# KeyInput_IJMEF.net
KiCad netlist of a schematic drawn in Altium Designer
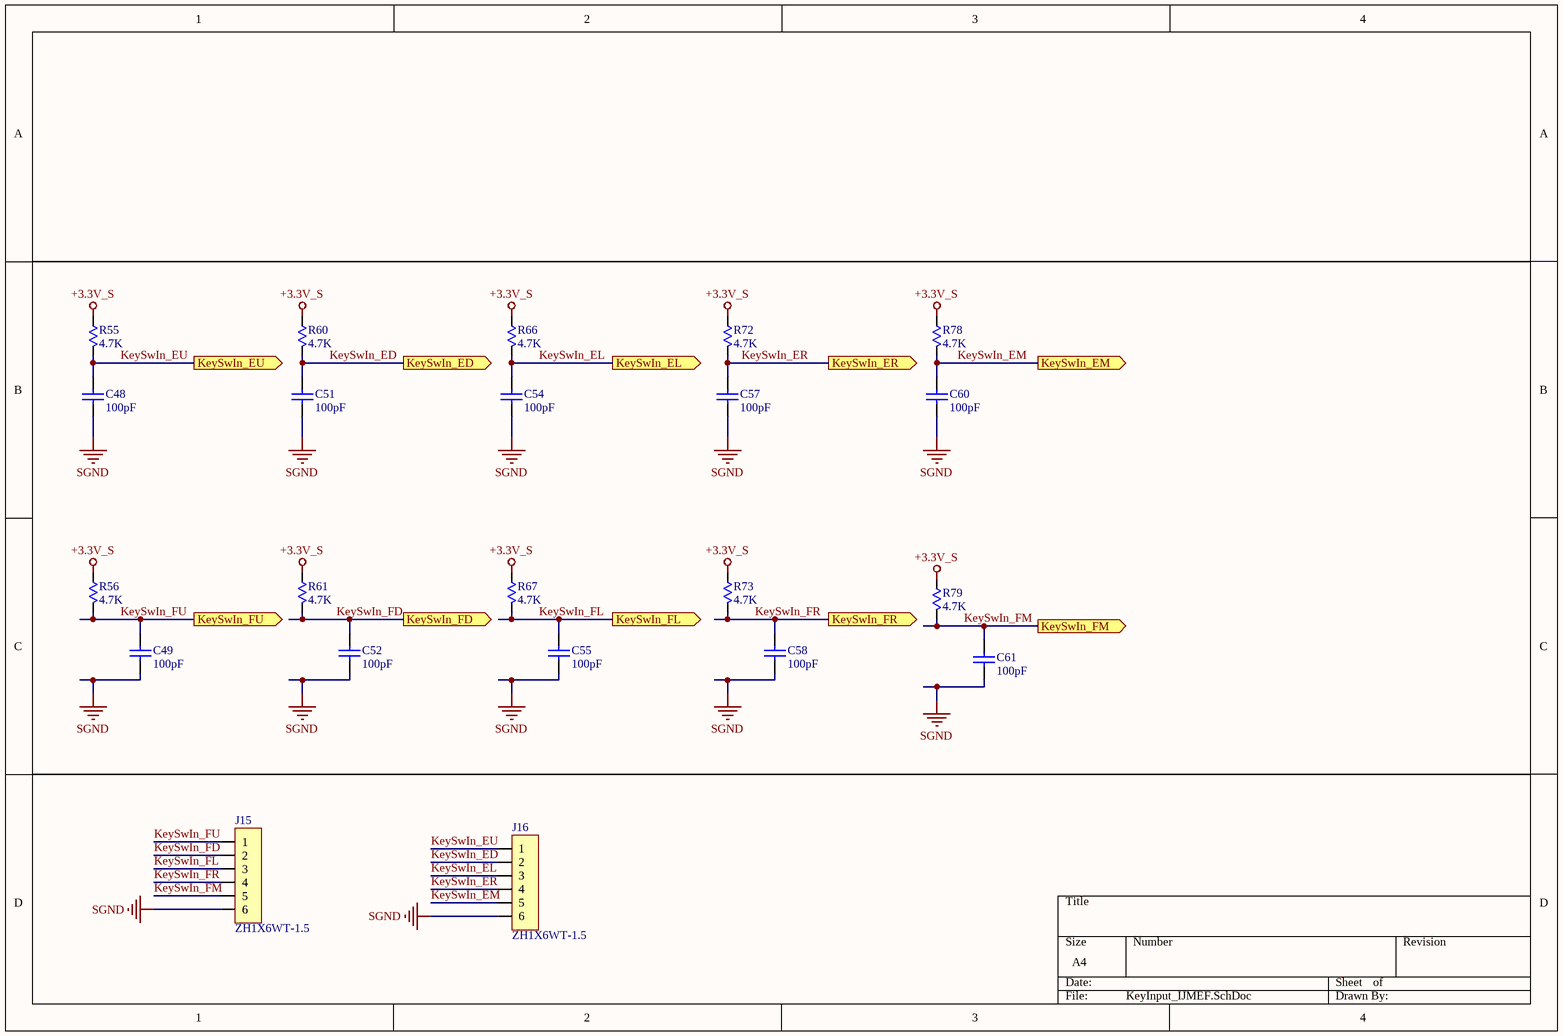
[diagram p0: KeyInput_IJMEF.SchDoc]

(export (version "E")
  (design (tool "Eeschema 10.0.6"))
  (components
    (comp (ref "C48")
      (value "100pF")
      (footprint "C0805")
      (description "Capacitor")
      (fields (field (name "PUBLISHER") "Altium Limited"))
      (libsource (lib "Miscellaneous Devices") (part "Cap"))
    )
    (comp (ref "C49")
      (value "100pF")
      (footprint "C0805")
      (description "Capacitor")
      (fields (field (name "PUBLISHER") "Altium Limited"))
      (libsource (lib "Miscellaneous Devices") (part "Cap"))
    )
    (comp (ref "C51")
      (value "100pF")
      (footprint "C0805")
      (description "Capacitor")
      (fields (field (name "PUBLISHER") "Altium Limited"))
      (libsource (lib "Miscellaneous Devices") (part "Cap"))
    )
    (comp (ref "C52")
      (value "100pF")
      (footprint "C0805")
      (description "Capacitor")
      (fields (field (name "PUBLISHER") "Altium Limited"))
      (libsource (lib "Miscellaneous Devices") (part "Cap"))
    )
    (comp (ref "C54")
      (value "100pF")
      (footprint "C0805")
      (description "Capacitor")
      (fields (field (name "PUBLISHER") "Altium Limited"))
      (libsource (lib "Miscellaneous Devices") (part "Cap"))
    )
    (comp (ref "C55")
      (value "100pF")
      (footprint "C0805")
      (description "Capacitor")
      (fields (field (name "PUBLISHER") "Altium Limited"))
      (libsource (lib "Miscellaneous Devices") (part "Cap"))
    )
    (comp (ref "C57")
      (value "100pF")
      (footprint "C0805")
      (description "Capacitor")
      (fields (field (name "PUBLISHER") "Altium Limited"))
      (libsource (lib "Miscellaneous Devices") (part "Cap"))
    )
    (comp (ref "C58")
      (value "100pF")
      (footprint "C0805")
      (description "Capacitor")
      (fields (field (name "PUBLISHER") "Altium Limited"))
      (libsource (lib "Miscellaneous Devices") (part "Cap"))
    )
    (comp (ref "C60")
      (value "100pF")
      (footprint "C0805")
      (description "Capacitor")
      (fields (field (name "PUBLISHER") "Altium Limited"))
      (libsource (lib "Miscellaneous Devices") (part "Cap"))
    )
    (comp (ref "C61")
      (value "100pF")
      (footprint "C0805")
      (description "Capacitor")
      (fields (field (name "PUBLISHER") "Altium Limited"))
      (libsource (lib "Miscellaneous Devices") (part "Cap"))
    )
    (comp (ref "J15")
      (value "ZH1X6WT-1.5")
      (footprint "ZH1X6WT-1.5")
      (libsource (lib "Connector Class") (part "HEADER1X6"))
    )
    (comp (ref "J16")
      (value "ZH1X6WT-1.5")
      (footprint "ZH1X6WT-1.5")
      (libsource (lib "Connector Class") (part "HEADER1X6"))
    )
    (comp (ref "R55")
      (value "4.7K")
      (footprint "R0805")
      (description "Resistor")
      (fields (field (name "PUBLISHER") "Altium Limited"))
      (libsource (lib "Passive Components Class") (part "RES"))
    )
    (comp (ref "R56")
      (value "4.7K")
      (footprint "R0805")
      (description "Resistor")
      (fields (field (name "PUBLISHER") "Altium Limited"))
      (libsource (lib "Passive Components Class") (part "RES"))
    )
    (comp (ref "R60")
      (value "4.7K")
      (footprint "R0805")
      (description "Resistor")
      (fields (field (name "PUBLISHER") "Altium Limited"))
      (libsource (lib "Passive Components Class") (part "RES"))
    )
    (comp (ref "R61")
      (value "4.7K")
      (footprint "R0805")
      (description "Resistor")
      (fields (field (name "PUBLISHER") "Altium Limited"))
      (libsource (lib "Passive Components Class") (part "RES"))
    )
    (comp (ref "R66")
      (value "4.7K")
      (footprint "R0805")
      (description "Resistor")
      (fields (field (name "PUBLISHER") "Altium Limited"))
      (libsource (lib "Passive Components Class") (part "RES"))
    )
    (comp (ref "R67")
      (value "4.7K")
      (footprint "R0805")
      (description "Resistor")
      (fields (field (name "PUBLISHER") "Altium Limited"))
      (libsource (lib "Passive Components Class") (part "RES"))
    )
    (comp (ref "R72")
      (value "4.7K")
      (footprint "R0805")
      (description "Resistor")
      (fields (field (name "PUBLISHER") "Altium Limited"))
      (libsource (lib "Passive Components Class") (part "RES"))
    )
    (comp (ref "R73")
      (value "4.7K")
      (footprint "R0805")
      (description "Resistor")
      (fields (field (name "PUBLISHER") "Altium Limited"))
      (libsource (lib "Passive Components Class") (part "RES"))
    )
    (comp (ref "R78")
      (value "4.7K")
      (footprint "R0805")
      (description "Resistor")
      (fields (field (name "PUBLISHER") "Altium Limited"))
      (libsource (lib "Passive Components Class") (part "RES"))
    )
    (comp (ref "R79")
      (value "4.7K")
      (footprint "R0805")
      (description "Resistor")
      (fields (field (name "PUBLISHER") "Altium Limited"))
      (libsource (lib "Passive Components Class") (part "RES"))
    )
  )
  (nets
    (net (code "1") (name "+3.3V_S") (class "Default")
      (node (ref "R55") (pin "2") (pinfunction "2_2") (pintype "passive"))
      (node (ref "R56") (pin "2") (pinfunction "2_2") (pintype "passive"))
      (node (ref "R60") (pin "2") (pinfunction "2_2") (pintype "passive"))
      (node (ref "R61") (pin "2") (pinfunction "2_2") (pintype "passive"))
      (node (ref "R66") (pin "2") (pinfunction "2_2") (pintype "passive"))
      (node (ref "R67") (pin "2") (pinfunction "2_2") (pintype "passive"))
      (node (ref "R72") (pin "2") (pinfunction "2_2") (pintype "passive"))
      (node (ref "R73") (pin "2") (pinfunction "2_2") (pintype "passive"))
      (node (ref "R78") (pin "2") (pinfunction "2_2") (pintype "passive"))
      (node (ref "R79") (pin "2") (pinfunction "2_2") (pintype "passive"))
    )
    (net (code "2") (name "/KeySwIn_ED") (class "Default")
      (node (ref "C51") (pin "1") (pinfunction "1_1") (pintype "passive"))
      (node (ref "J16") (pin "2") (pinfunction "2_2") (pintype "passive"))
      (node (ref "R60") (pin "1") (pinfunction "1_1") (pintype "passive"))
    )
    (net (code "3") (name "/KeySwIn_EL") (class "Default")
      (node (ref "C54") (pin "1") (pinfunction "1_1") (pintype "passive"))
      (node (ref "J16") (pin "3") (pinfunction "3_3") (pintype "passive"))
      (node (ref "R66") (pin "1") (pinfunction "1_1") (pintype "passive"))
    )
    (net (code "4") (name "/KeySwIn_EM") (class "Default")
      (node (ref "C60") (pin "1") (pinfunction "1_1") (pintype "passive"))
      (node (ref "J16") (pin "5") (pinfunction "5_5") (pintype "passive"))
      (node (ref "R78") (pin "1") (pinfunction "1_1") (pintype "passive"))
    )
    (net (code "5") (name "/KeySwIn_ER") (class "Default")
      (node (ref "C57") (pin "1") (pinfunction "1_1") (pintype "passive"))
      (node (ref "J16") (pin "4") (pinfunction "4_4") (pintype "passive"))
      (node (ref "R72") (pin "1") (pinfunction "1_1") (pintype "passive"))
    )
    (net (code "6") (name "/KeySwIn_EU") (class "Default")
      (node (ref "C48") (pin "1") (pinfunction "1_1") (pintype "passive"))
      (node (ref "J16") (pin "1") (pinfunction "1_1") (pintype "passive"))
      (node (ref "R55") (pin "1") (pinfunction "1_1") (pintype "passive"))
    )
    (net (code "7") (name "/KeySwIn_FD") (class "Default")
      (node (ref "C52") (pin "1") (pinfunction "1_1") (pintype "passive"))
      (node (ref "J15") (pin "2") (pinfunction "2_2") (pintype "passive"))
      (node (ref "R61") (pin "1") (pinfunction "1_1") (pintype "passive"))
    )
    (net (code "8") (name "/KeySwIn_FL") (class "Default")
      (node (ref "C55") (pin "1") (pinfunction "1_1") (pintype "passive"))
      (node (ref "J15") (pin "3") (pinfunction "3_3") (pintype "passive"))
      (node (ref "R67") (pin "1") (pinfunction "1_1") (pintype "passive"))
    )
    (net (code "9") (name "/KeySwIn_FM") (class "Default")
      (node (ref "C61") (pin "1") (pinfunction "1_1") (pintype "passive"))
      (node (ref "J15") (pin "5") (pinfunction "5_5") (pintype "passive"))
      (node (ref "R79") (pin "1") (pinfunction "1_1") (pintype "passive"))
    )
    (net (code "10") (name "/KeySwIn_FR") (class "Default")
      (node (ref "C58") (pin "1") (pinfunction "1_1") (pintype "passive"))
      (node (ref "J15") (pin "4") (pinfunction "4_4") (pintype "passive"))
      (node (ref "R73") (pin "1") (pinfunction "1_1") (pintype "passive"))
    )
    (net (code "11") (name "/KeySwIn_FU") (class "Default")
      (node (ref "C49") (pin "1") (pinfunction "1_1") (pintype "passive"))
      (node (ref "J15") (pin "1") (pinfunction "1_1") (pintype "passive"))
      (node (ref "R56") (pin "1") (pinfunction "1_1") (pintype "passive"))
    )
    (net (code "12") (name "SGND") (class "Default")
      (node (ref "C48") (pin "2") (pinfunction "2_2") (pintype "passive"))
      (node (ref "C49") (pin "2") (pinfunction "2_2") (pintype "passive"))
      (node (ref "C51") (pin "2") (pinfunction "2_2") (pintype "passive"))
      (node (ref "C52") (pin "2") (pinfunction "2_2") (pintype "passive"))
      (node (ref "C54") (pin "2") (pinfunction "2_2") (pintype "passive"))
      (node (ref "C55") (pin "2") (pinfunction "2_2") (pintype "passive"))
      (node (ref "C57") (pin "2") (pinfunction "2_2") (pintype "passive"))
      (node (ref "C58") (pin "2") (pinfunction "2_2") (pintype "passive"))
      (node (ref "C60") (pin "2") (pinfunction "2_2") (pintype "passive"))
      (node (ref "C61") (pin "2") (pinfunction "2_2") (pintype "passive"))
      (node (ref "J15") (pin "6") (pinfunction "6_6") (pintype "passive"))
      (node (ref "J16") (pin "6") (pinfunction "6_6") (pintype "passive"))
    )
  )
)
